# Sheet1.net
KiCad netlist of a schematic drawn in Altium Designer
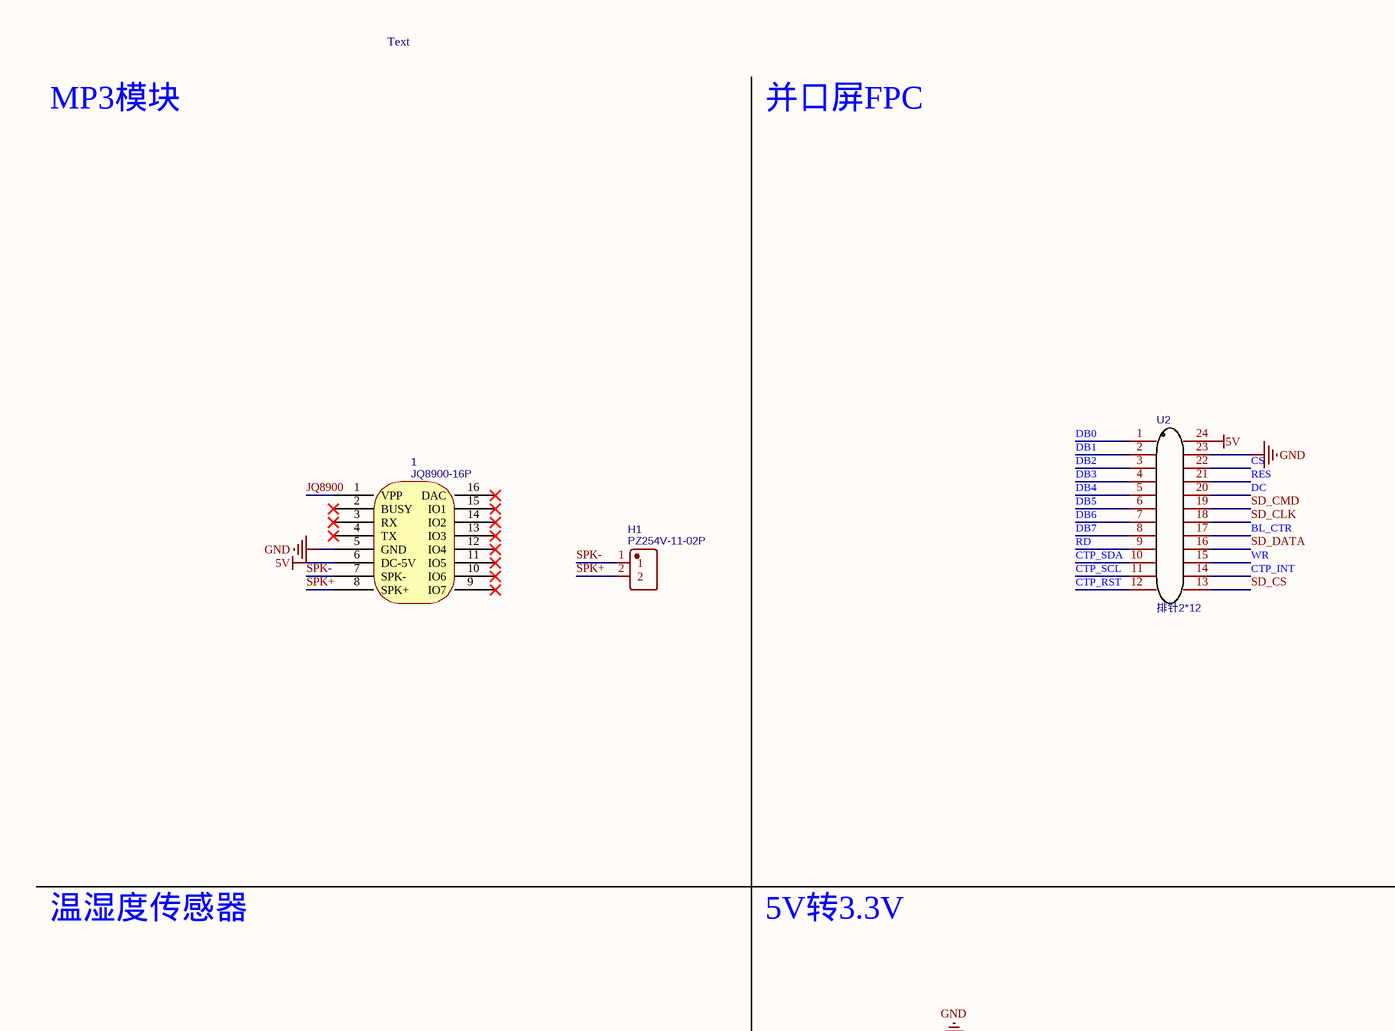
[diagram p0: Sheet1.SchDoc, top left]
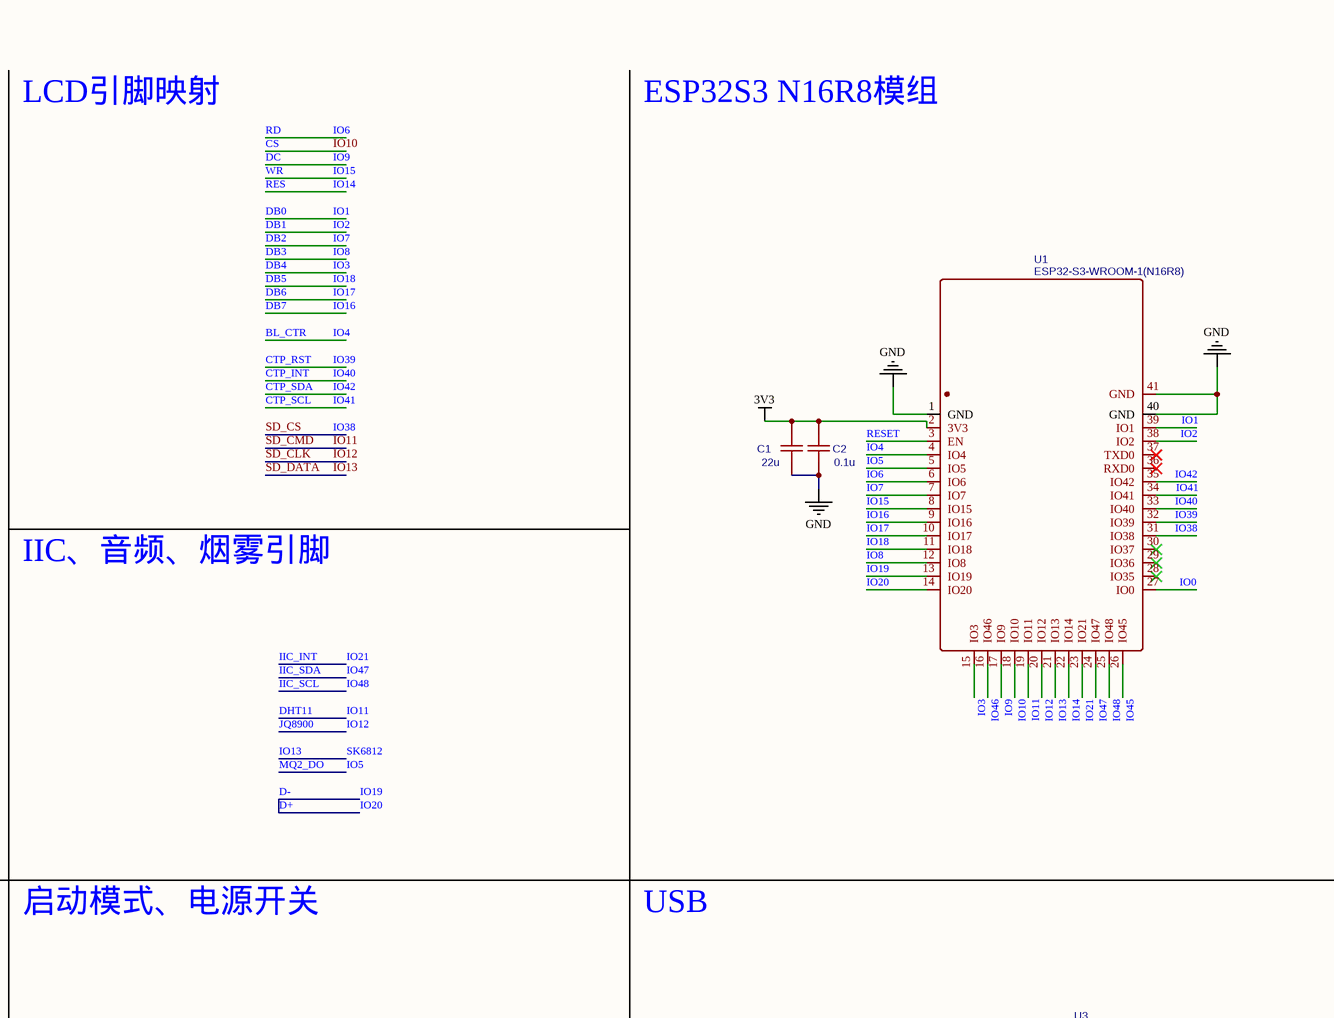
[diagram p1: Sheet1.SchDoc, top right]
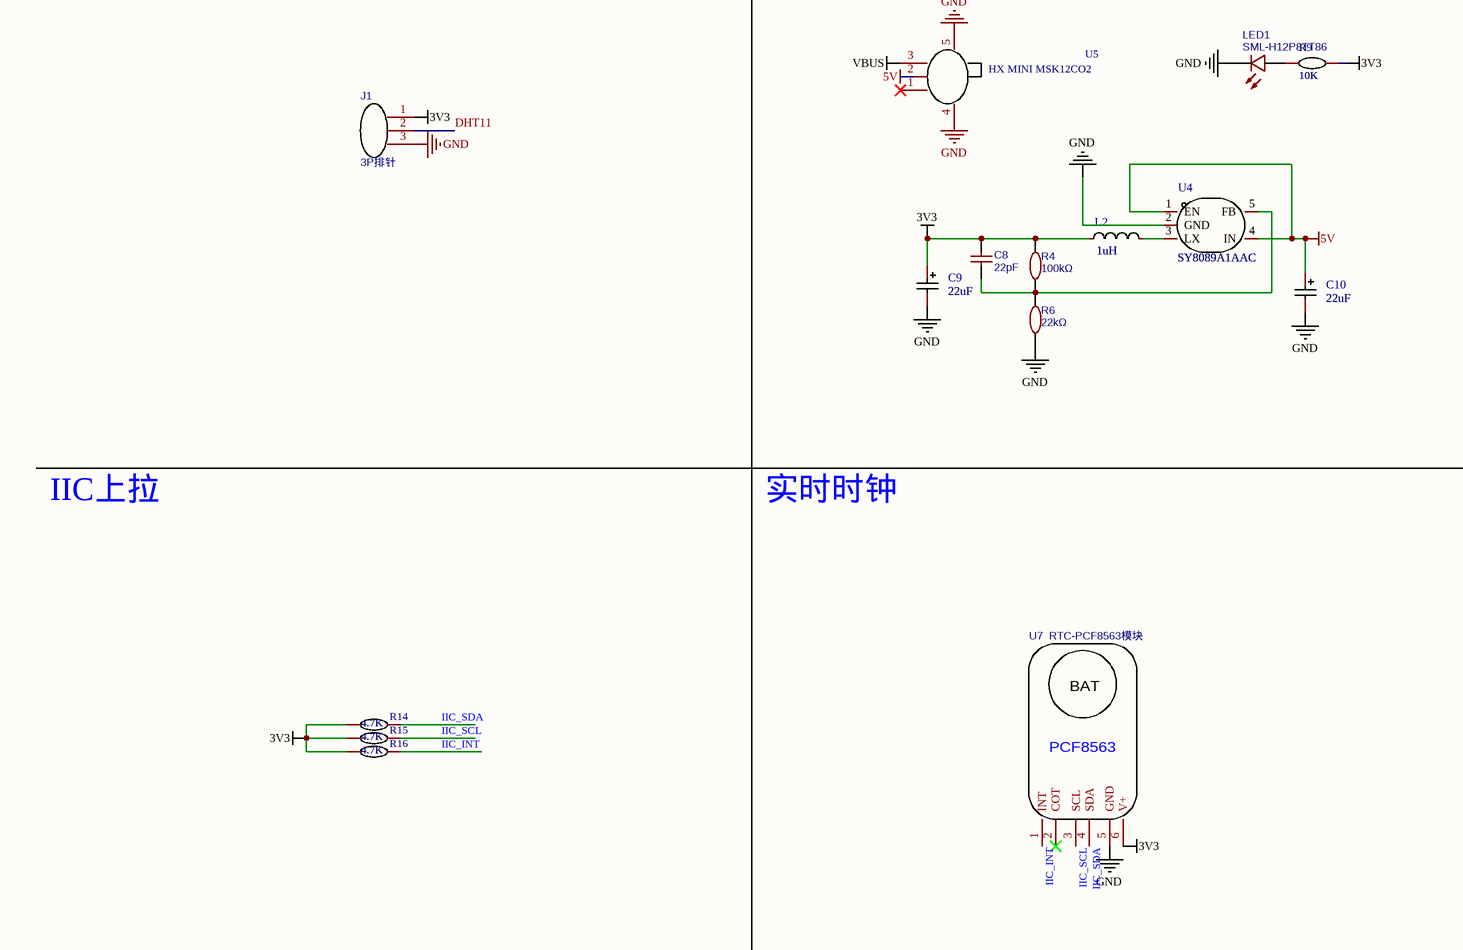
[diagram p2: Sheet1.SchDoc, bottom left]
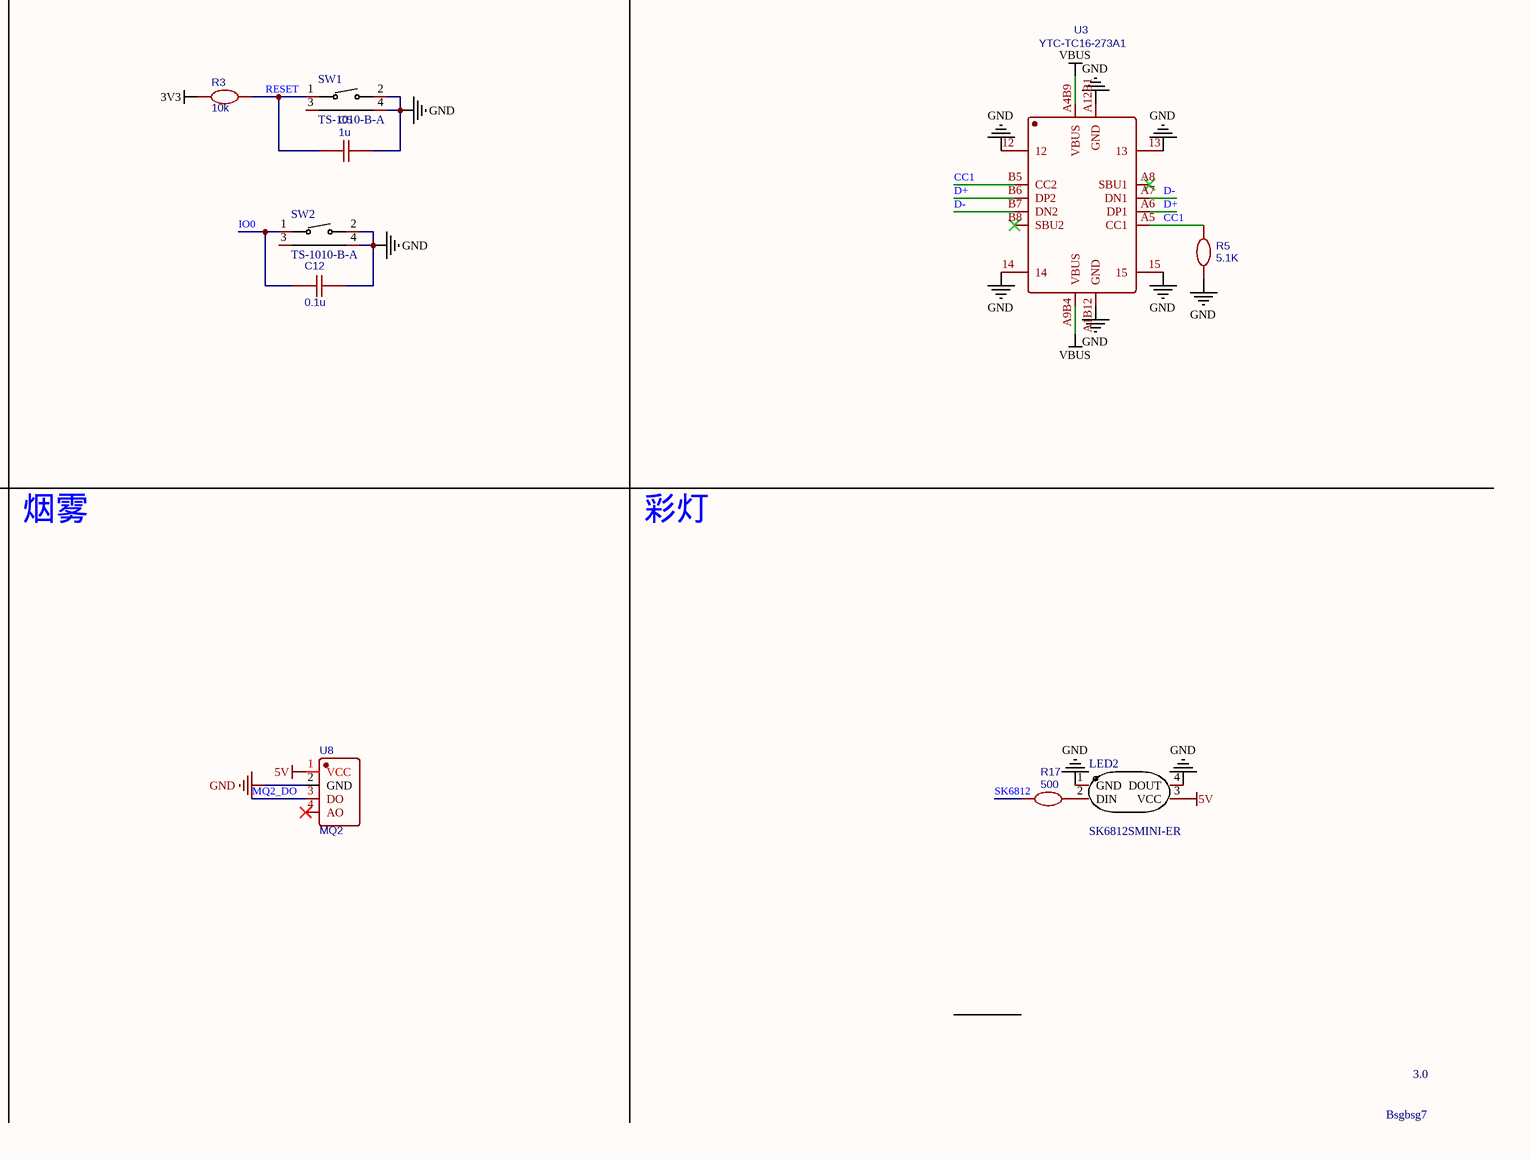
[diagram p3: Sheet1.SchDoc, bottom right]

(export (version "E")
  (design (tool "Eeschema 10.0.6"))
  (components
    (comp (ref "1")
      (value "JQ8900-16P")
      (footprint "JQ8900-16P")
      (fields (field (name "CONTRIBUTOR") "gfd1"))
      (libsource (lib "altium-import") (part "root_0_JQ8900-16P_"))
    )
    (comp (ref "C1")
      (value "22u")
      (footprint "C0603")
      (fields (field (name "CONTRIBUTOR") "LCEDA_Lib"))
      (libsource (lib "altium-import") (part "root_3_22u_"))
    )
    (comp (ref "C2")
      (value "0.1u")
      (footprint "C0603")
      (fields (field (name "CONTRIBUTOR") "LCEDA_Lib"))
      (libsource (lib "altium-import") (part "root_1_0.1u_"))
    )
    (comp (ref "C5")
      (value "1u")
      (footprint "C0603")
      (fields (field (name "CONTRIBUTOR") "LCEDA_Lib"))
      (libsource (lib "altium-import") (part "root_0_1u_"))
    )
    (comp (ref "C8")
      (value "22pF")
      (footprint "C0603")
      (fields
        (field (name "BOM_MANUFACTURER PART") "CL10C220JB8NNNC")
        (field (name "BOM_SUPPLIER PART") "C1653")
      )
      (libsource (lib "Schlib1") (part "22pF"))
    )
    (comp (ref "C9")
      (value "22uF")
      (footprint "CASE-B_3528")
      (description "容值:22uF;精度:±10%;额定电压:16V;等效串联电阻:2.3Ω@100kHz;工作温度:-55℃~+125℃;")
      (fields
        (field (name "NAME") "22uF")
        (field (name "MANUFACTURER") "Kyocera AVX")
        (field (name "MANUFACTURER PART") "TAJB226K016RNJ")
      )
      (libsource (lib "altium-import") (part "root_1_TAJB226K016RNJ_"))
    )
    (comp (ref "C10")
      (value "22uF")
      (footprint "CASE-B_3528")
      (description "容值:22uF;精度:±10%;额定电压:16V;等效串联电阻:2.3Ω@100kHz;工作温度:-55℃~+125℃;")
      (fields
        (field (name "NAME") "22uF")
        (field (name "MANUFACTURER") "Kyocera AVX")
        (field (name "MANUFACTURER PART") "TAJB226K016RNJ")
      )
      (libsource (lib "altium-import") (part "root_1_TAJB226K016RNJ_"))
    )
    (comp (ref "C12")
      (value "0.1u")
      (footprint "C0603")
      (fields (field (name "CONTRIBUTOR") "LCEDA_Lib"))
      (libsource (lib "altium-import") (part "root_2_0.1u_"))
    )
    (comp (ref "H1")
      (value "PZ254V-11-02P")
      (footprint "HDR-TH_2P-P2.54-V-M")
      (fields (field (name "BOM_SUPPLIER PART") "C492401") (field (name "CONTRIBUTOR") "LCSC"))
      (libsource (lib "altium-import") (part "root_0_PZ254V-11-02P_"))
    )
    (comp (ref "J1")
      (value "3P排针")
      (footprint "DHT")
      (fields (field (name "CONTRIBUTOR") "878738424"))
      (libsource (lib "Schlib1") (part "3P排针"))
    )
    (comp (ref "L2")
      (value "1uH")
      (footprint "IND-SMD_L3.2-W3.2-1")
      (description "电感值:1uH;精度:±20%;额定电流:4A;直流电阻(DCR):32mΩ;")
      (fields
        (field (name "NAME") "1uH")
        (field (name "MANUFACTURER") "TAI-TECH(台庆)")
        (field (name "MANUFACTURER PART") "TMPC0302H-1R0MG")
      )
      (libsource (lib "altium-import") (part "root_0_TMPC0302H-1R0MG_"))
    )
    (comp (ref "LED1")
      (value "SML-H12P8TT86")
      (footprint "LED0805-R-RD_GREEN")
      (fields (field (name "BOM_SUPPLIER PART") "C510035") (field (name "CONTRIBUTOR") "lcsc"))
      (libsource (lib "altium-import") (part "root_2_SML-H12P8TT86_"))
    )
    (comp (ref "LED2")
      (value "SK6812SMINI-ER")
      (footprint "SK6812")
      (fields (field (name "MANUFACTURER") "欧思科光电") (field (name "NAME") "SK6812SMINI-ER"))
      (libsource (lib "Integrated_Library1") (part "SK6812SMINI-ER"))
    )
    (comp (ref "R3")
      (value "10k")
      (footprint "R0603")
      (fields (field (name "CONTRIBUTOR") "LCEDA_Lib"))
      (libsource (lib "altium-import") (part "root_0_5.1K_"))
    )
    (comp (ref "R4")
      (value "100kΩ")
      (footprint "R0603")
      (fields
        (field (name "BOM_MANUFACTURER PART") "0603WAF1003T5E")
        (field (name "BOM_SUPPLIER PART") "C25803")
      )
      (libsource (lib "Schlib1") (part "100kΩ"))
    )
    (comp (ref "R5")
      (value "5.1K")
      (footprint "R0603")
      (fields (field (name "CONTRIBUTOR") "LCEDA_Lib"))
      (libsource (lib "altium-import") (part "root_3_5.1K_"))
    )
    (comp (ref "R6")
      (value "22kΩ")
      (footprint "R0603")
      (fields
        (field (name "BOM_MANUFACTURER PART") "0603WAF2202T5E")
        (field (name "BOM_SUPPLIER PART") "C31850")
      )
      (libsource (lib "Schlib1") (part "22kΩ"))
    )
    (comp (ref "R9") (value "10K") (footprint "R0603") (libsource (lib "altium-import") (part "root_0_10K_")))
    (comp (ref "R14")
      (value "4.7K")
      (footprint "R0603")
      (fields (field (name "MANUFACTURER") "YAGEO") (field (name "MANUFACTURER PART") "AF0603FR-0710KL"))
      (libsource (lib "altium-import") (part "root_0_4.7K_"))
    )
    (comp (ref "R15")
      (value "4.7K")
      (footprint "R0603")
      (fields (field (name "MANUFACTURER") "YAGEO") (field (name "MANUFACTURER PART") "AF0603FR-0710KL"))
      (libsource (lib "altium-import") (part "root_0_4.7K_"))
    )
    (comp (ref "R16")
      (value "4.7K")
      (footprint "R0603")
      (fields (field (name "MANUFACTURER") "YAGEO") (field (name "MANUFACTURER PART") "AF0603FR-0710KL"))
      (libsource (lib "altium-import") (part "root_0_4.7K_"))
    )
    (comp (ref "R17")
      (value "500")
      (footprint "R0603")
      (fields (field (name "CONTRIBUTOR") "LCEDA_Lib"))
      (libsource (lib "altium-import") (part "root_0_1.2K_"))
    )
    (comp (ref "SW1")
      (value "TS-1010-B-A")
      (footprint "PcbLib1:KEY-SMD_TX-1010-X-X")
      (fields (field (name "MANUFACTURER") "XKB Connectivity(中国星坤)"))
      (libsource (lib "Integrated_Library1") (part "TS-1010-B-A"))
    )
    (comp (ref "SW2")
      (value "TS-1010-B-A")
      (footprint "PcbLib1:KEY-SMD_TX-1010-X-X")
      (fields (field (name "MANUFACTURER") "XKB Connectivity(中国星坤)"))
      (libsource (lib "Integrated_Library1") (part "TS-1010-B-A"))
    )
    (comp (ref "U1")
      (value "ESP32-S3-WROOM-1(N16R8)")
      (footprint "WIRELM-SMD_ESP32-S3-WROOM-1")
      (fields
        (field (name "BOM_SUPPLIER PART") "C2913202")
        (field (name "BOM_MANUFACTURER PART") "ESP32-S3-WROOM-1-N16R8")
        (field (name "CONTRIBUTOR") "lcsc")
      )
      (libsource (lib "altium-import") (part "root_0_ESP32-S3-WROOM-1(N16R8)_"))
    )
    (comp (ref "U2")
      (value "排针2*12")
      (footprint "PCBComponent_1 - duplicate")
      (fields (field (name "CONTRIBUTOR") "Leshushi"))
      (libsource (lib "Schlib1") (part "排针2*12"))
    )
    (comp (ref "U3")
      (value "YTC-TC16-273A1")
      (footprint "TYPE-C-SMD_YIYUAN_YTC-TC16-273A1")
      (fields (field (name "BOM_SUPPLIER PART") "C5260486") (field (name "CONTRIBUTOR") "lcsc"))
      (libsource (lib "altium-import") (part "root_0_YTC-TC16-273A1_"))
    )
    (comp (ref "U4")
      (value "SY8089A1AAC")
      (footprint "TSOT-23-5_L2.9-W1.6-P0.95-LS2.8-BR")
      (fields (field (name "NAME") "SY8089A1AAC") (field (name "MANUFACTURER") "silergy(矽力杰)"))
      (libsource (lib "altium-import") (part "root_0_SY8089A1AAC_"))
    )
    (comp (ref "U5")
      (value "HX MINI MSK12CO2")
      (footprint "SW-SMD_MSK12CO2")
      (fields (field (name "MANUFACTURER") "hanxia(韩下)"))
      (libsource (lib "Schlib1") (part "HX MINI MSK12CO2"))
    )
    (comp (ref "U7")
      (value "RTC-PCF8563模块")
      (footprint "PCF8563模块")
      (fields (field (name "BOM_MANUFACTURER PART") "Xu4388") (field (name "CONTRIBUTOR") "XDesign"))
      (libsource (lib "Integrated_Library1") (part "RTC-PCF8563模块"))
    )
    (comp (ref "U8")
      (value "MQ2")
      (footprint "MQ2")
      (fields (field (name "CONTRIBUTOR") "1898stark"))
      (libsource (lib "Integrated_Library1") (part "MQ2"))
    )
  )
  (nets
    (net (code "1") (name "/BL_CTR") (class "Default")
      (node (ref "U1") (pin "4") (pinfunction "IO4_4") (pintype "passive"))
      (node (ref "U2") (pin "17") (pinfunction "17_17") (pintype "passive"))
    )
    (net (code "2") (name "/CC1") (class "Default")
      (node (ref "R5") (pin "1") (pinfunction "1_1") (pintype "passive"))
      (node (ref "U3") (pin "A5") (pinfunction "CC1_A5") (pintype "passive"))
      (node (ref "U3") (pin "B5") (pinfunction "CC2_B5") (pintype "passive"))
    )
    (net (code "3") (name "/CS") (class "Default")
      (node (ref "U1") (pin "18") (pinfunction "IO10_18") (pintype "passive"))
      (node (ref "U2") (pin "22") (pinfunction "22_22") (pintype "passive"))
    )
    (net (code "4") (name "/CTP_INT") (class "Default")
      (node (ref "U1") (pin "33") (pinfunction "IO40_33") (pintype "passive"))
      (node (ref "U2") (pin "14") (pinfunction "14_14") (pintype "passive"))
    )
    (net (code "5") (name "/CTP_RST") (class "Default")
      (node (ref "U1") (pin "32") (pinfunction "IO39_32") (pintype "passive"))
      (node (ref "U2") (pin "12") (pinfunction "12_12") (pintype "passive"))
    )
    (net (code "6") (name "/CTP_SCL") (class "Default")
      (node (ref "U1") (pin "34") (pinfunction "IO41_34") (pintype "passive"))
      (node (ref "U2") (pin "11") (pinfunction "11_11") (pintype "passive"))
    )
    (net (code "7") (name "/CTP_SDA") (class "Default")
      (node (ref "U1") (pin "35") (pinfunction "IO42_35") (pintype "passive"))
      (node (ref "U2") (pin "10") (pinfunction "10_10") (pintype "passive"))
    )
    (net (code "8") (name "/D+") (class "Default")
      (node (ref "U1") (pin "13") (pinfunction "IO19_13") (pintype "passive"))
      (node (ref "U1") (pin "14") (pinfunction "IO20_14") (pintype "passive"))
      (node (ref "U3") (pin "A6") (pinfunction "DP1_A6") (pintype "passive"))
      (node (ref "U3") (pin "A7") (pinfunction "DN1_A7") (pintype "passive"))
      (node (ref "U3") (pin "B6") (pinfunction "DP2_B6") (pintype "passive"))
      (node (ref "U3") (pin "B7") (pinfunction "DN2_B7") (pintype "passive"))
    )
    (net (code "9") (name "/DB0") (class "Default")
      (node (ref "U1") (pin "39") (pinfunction "IO1_39") (pintype "passive"))
      (node (ref "U2") (pin "1") (pinfunction "1_1") (pintype "passive"))
    )
    (net (code "10") (name "/DB1") (class "Default")
      (node (ref "U1") (pin "38") (pinfunction "IO2_38") (pintype "passive"))
      (node (ref "U2") (pin "2") (pinfunction "2_2") (pintype "passive"))
    )
    (net (code "11") (name "/DB2") (class "Default")
      (node (ref "U1") (pin "7") (pinfunction "IO7_7") (pintype "passive"))
      (node (ref "U2") (pin "3") (pinfunction "3_3") (pintype "passive"))
    )
    (net (code "12") (name "/DB3") (class "Default")
      (node (ref "U1") (pin "12") (pinfunction "IO8_12") (pintype "passive"))
      (node (ref "U2") (pin "4") (pinfunction "4_4") (pintype "passive"))
    )
    (net (code "13") (name "/DB4") (class "Default")
      (node (ref "U1") (pin "15") (pinfunction "IO3_15") (pintype "passive"))
      (node (ref "U2") (pin "5") (pinfunction "5_5") (pintype "passive"))
    )
    (net (code "14") (name "/DB5") (class "Default")
      (node (ref "U1") (pin "11") (pinfunction "IO18_11") (pintype "passive"))
      (node (ref "U2") (pin "6") (pinfunction "6_6") (pintype "passive"))
    )
    (net (code "15") (name "/DB6") (class "Default")
      (node (ref "U1") (pin "10") (pinfunction "IO17_10") (pintype "passive"))
      (node (ref "U2") (pin "7") (pinfunction "7_7") (pintype "passive"))
    )
    (net (code "16") (name "/DB7") (class "Default")
      (node (ref "U1") (pin "9") (pinfunction "IO16_9") (pintype "passive"))
      (node (ref "U2") (pin "8") (pinfunction "8_8") (pintype "passive"))
    )
    (net (code "17") (name "/DC") (class "Default")
      (node (ref "U1") (pin "17") (pinfunction "IO9_17") (pintype "passive"))
      (node (ref "U2") (pin "20") (pinfunction "20_20") (pintype "passive"))
    )
    (net (code "18") (name "/DHT11") (class "Default")
      (node (ref "J1") (pin "2") (pinfunction "2_2") (pintype "passive"))
      (node (ref "U1") (pin "19") (pinfunction "IO11_19") (pintype "passive"))
      (node (ref "U2") (pin "19") (pinfunction "19_19") (pintype "passive"))
    )
    (net (code "19") (name "/IIC_INT") (class "Default")
      (node (ref "R16") (pin "2") (pinfunction "2_2") (pintype "passive"))
      (node (ref "U1") (pin "23") (pinfunction "IO21_23") (pintype "passive"))
      (node (ref "U7") (pin "1") (pinfunction "INT_1") (pintype "passive"))
    )
    (net (code "20") (name "/IIC_SCL") (class "Default")
      (node (ref "R15") (pin "2") (pinfunction "2_2") (pintype "passive"))
      (node (ref "U1") (pin "25") (pinfunction "IO48_25") (pintype "passive"))
      (node (ref "U7") (pin "3") (pinfunction "SCL_3") (pintype "passive"))
    )
    (net (code "21") (name "/IIC_SDA") (class "Default")
      (node (ref "R14") (pin "2") (pinfunction "2_2") (pintype "passive"))
      (node (ref "U1") (pin "24") (pinfunction "IO47_24") (pintype "passive"))
      (node (ref "U7") (pin "4") (pinfunction "SDA_4") (pintype "passive"))
    )
    (net (code "22") (name "/IO0") (class "Default")
      (node (ref "C12") (pin "2") (pinfunction "2_2") (pintype "passive"))
      (node (ref "SW2") (pin "1") (pinfunction "1_1") (pintype "passive"))
      (node (ref "U1") (pin "27") (pinfunction "IO0_27") (pintype "passive"))
    )
    (net (code "23") (name "/IO5") (class "Default")
      (node (ref "U1") (pin "5") (pinfunction "IO5_5") (pintype "passive"))
      (node (ref "U8") (pin "3") (pinfunction "DO_3") (pintype "passive"))
    )
    (net (code "24") (name "/IO6") (class "Default")
      (node (ref "U1") (pin "6") (pinfunction "IO6_6") (pintype "passive"))
      (node (ref "U2") (pin "9") (pinfunction "9_9") (pintype "passive"))
    )
    (net (code "25") (name "/IO12") (class "Default")
      (node (ref "1") (pin "1") (pinfunction "VPP_1") (pintype "passive"))
      (node (ref "U1") (pin "20") (pinfunction "IO12_20") (pintype "passive"))
      (node (ref "U2") (pin "18") (pinfunction "18_18") (pintype "passive"))
    )
    (net (code "26") (name "/IO13") (class "Default")
      (node (ref "R17") (pin "1") (pinfunction "1_1") (pintype "passive"))
      (node (ref "U1") (pin "21") (pinfunction "IO13_21") (pintype "passive"))
      (node (ref "U2") (pin "16") (pinfunction "16_16") (pintype "passive"))
    )
    (net (code "27") (name "/IO14") (class "Default")
      (node (ref "U1") (pin "22") (pinfunction "IO14_22") (pintype "passive"))
      (node (ref "U2") (pin "21") (pinfunction "21_21") (pintype "passive"))
    )
    (net (code "28") (name "/IO15") (class "Default")
      (node (ref "U1") (pin "8") (pinfunction "IO15_8") (pintype "passive"))
      (node (ref "U2") (pin "15") (pinfunction "15_15") (pintype "passive"))
    )
    (net (code "29") (name "/IO38") (class "Default")
      (node (ref "U1") (pin "31") (pinfunction "IO38_31") (pintype "passive"))
      (node (ref "U2") (pin "13") (pinfunction "13_13") (pintype "passive"))
    )
    (net (code "30") (name "/IO45") (class "Default")
      (node (ref "U1") (pin "26") (pinfunction "IO45_26") (pintype "passive"))
    )
    (net (code "31") (name "/IO46") (class "Default")
      (node (ref "U1") (pin "16") (pinfunction "IO46_16") (pintype "passive"))
    )
    (net (code "32") (name "/RESET") (class "Default")
      (node (ref "C5") (pin "1") (pinfunction "1_1") (pintype "passive"))
      (node (ref "R3") (pin "2") (pinfunction "2_2") (pintype "passive"))
      (node (ref "SW1") (pin "1") (pinfunction "1_1") (pintype "passive"))
      (node (ref "U1") (pin "3") (pinfunction "EN_3") (pintype "passive"))
    )
    (net (code "33") (name "/SPK+") (class "Default")
      (node (ref "1") (pin "8") (pinfunction "SPK+_8") (pintype "passive"))
      (node (ref "H1") (pin "2") (pinfunction "2_2") (pintype "passive"))
    )
    (net (code "34") (name "/SPK-") (class "Default")
      (node (ref "1") (pin "7") (pinfunction "SPK-_7") (pintype "passive"))
      (node (ref "H1") (pin "1") (pinfunction "1_1") (pintype "passive"))
    )
    (net (code "35") (name "3V3") (class "Default")
      (node (ref "C1") (pin "1") (pinfunction "1_1") (pintype "passive"))
      (node (ref "C2") (pin "2") (pinfunction "2_2") (pintype "passive"))
      (node (ref "C8") (pin "2") (pinfunction "2_2") (pintype "passive"))
      (node (ref "C9") (pin "1") (pinfunction "1_1") (pintype "passive"))
      (node (ref "J1") (pin "1") (pinfunction "1_1") (pintype "passive"))
      (node (ref "L2") (pin "1") (pinfunction "1_1") (pintype "passive"))
      (node (ref "R14") (pin "1") (pinfunction "1_1") (pintype "passive"))
      (node (ref "R15") (pin "1") (pinfunction "1_1") (pintype "passive"))
      (node (ref "R16") (pin "1") (pinfunction "1_1") (pintype "passive"))
      (node (ref "R3") (pin "1") (pinfunction "1_1") (pintype "passive"))
      (node (ref "R4") (pin "2") (pinfunction "2_2") (pintype "passive"))
      (node (ref "R9") (pin "2") (pinfunction "2_2") (pintype "passive"))
      (node (ref "U1") (pin "2") (pinfunction "3V3_2") (pintype "passive"))
      (node (ref "U7") (pin "6") (pinfunction "V+_6") (pintype "passive"))
    )
    (net (code "36") (name "5V") (class "Default")
      (node (ref "1") (pin "6") (pinfunction "DC-5V_6") (pintype "passive"))
      (node (ref "C10") (pin "1") (pinfunction "1_1") (pintype "passive"))
      (node (ref "LED2") (pin "3") (pinfunction "VCC_3") (pintype "passive"))
      (node (ref "U2") (pin "24") (pinfunction "24_24") (pintype "passive"))
      (node (ref "U4") (pin "1") (pinfunction "EN_1") (pintype "passive"))
      (node (ref "U4") (pin "4") (pinfunction "IN_4") (pintype "passive"))
      (node (ref "U5") (pin "2") (pinfunction "2_2") (pintype "passive"))
      (node (ref "U8") (pin "1") (pinfunction "VCC_1") (pintype "passive"))
    )
    (net (code "37") (name "GND") (class "Default")
      (node (ref "1") (pin "5") (pinfunction "GND_5") (pintype "passive"))
      (node (ref "C1") (pin "2") (pinfunction "2_2") (pintype "passive"))
      (node (ref "C10") (pin "2") (pinfunction "2_2") (pintype "passive"))
      (node (ref "C12") (pin "1") (pinfunction "1_1") (pintype "passive"))
      (node (ref "C2") (pin "1") (pinfunction "1_1") (pintype "passive"))
      (node (ref "C5") (pin "2") (pinfunction "2_2") (pintype "passive"))
      (node (ref "C9") (pin "2") (pinfunction "2_2") (pintype "passive"))
      (node (ref "J1") (pin "3") (pinfunction "3_3") (pintype "passive"))
      (node (ref "LED1") (pin "2") (pinfunction "C_2") (pintype "passive"))
      (node (ref "LED2") (pin "1") (pinfunction "GND_1") (pintype "passive"))
      (node (ref "LED2") (pin "4") (pinfunction "DOUT_4") (pintype "passive"))
      (node (ref "R5") (pin "2") (pinfunction "2_2") (pintype "passive"))
      (node (ref "R6") (pin "1") (pinfunction "1_1") (pintype "passive"))
      (node (ref "SW1") (pin "2") (pinfunction "2_2") (pintype "passive"))
      (node (ref "SW1") (pin "4") (pinfunction "4_4") (pintype "passive"))
      (node (ref "SW2") (pin "2") (pinfunction "2_2") (pintype "passive"))
      (node (ref "SW2") (pin "4") (pinfunction "4_4") (pintype "passive"))
      (node (ref "U1") (pin "1") (pinfunction "GND_1") (pintype "passive"))
      (node (ref "U1") (pin "40") (pinfunction "GND_40") (pintype "passive"))
      (node (ref "U1") (pin "41") (pinfunction "GND_41") (pintype "passive"))
      (node (ref "U2") (pin "23") (pinfunction "23_23") (pintype "passive"))
      (node (ref "U3") (pin "12") (pinfunction "12_12") (pintype "passive"))
      (node (ref "U3") (pin "13") (pinfunction "13_13") (pintype "passive"))
      (node (ref "U3") (pin "14") (pinfunction "14_14") (pintype "passive"))
      (node (ref "U3") (pin "15") (pinfunction "15_15") (pintype "passive"))
      (node (ref "U3") (pin "A12B1") (pinfunction "GND_A12B1") (pintype "passive"))
      (node (ref "U3") (pin "A1B12") (pinfunction "GND_A1B12") (pintype "passive"))
      (node (ref "U4") (pin "2") (pinfunction "GND_2") (pintype "passive"))
      (node (ref "U5") (pin "4") (pinfunction "4_4") (pintype "passive"))
      (node (ref "U5") (pin "5") (pinfunction "5_5") (pintype "passive"))
      (node (ref "U7") (pin "5") (pinfunction "GND_5") (pintype "passive"))
      (node (ref "U8") (pin "2") (pinfunction "GND_2") (pintype "passive"))
    )
    (net (code "38") (name "Net-(LED1-A)") (class "Default")
      (node (ref "LED1") (pin "1") (pinfunction "A_1") (pintype "passive"))
      (node (ref "R9") (pin "1") (pinfunction "1_1") (pintype "passive"))
    )
    (net (code "39") (name "Net-(LED2-DIN)") (class "Default")
      (node (ref "LED2") (pin "2") (pinfunction "DIN_2") (pintype "passive"))
      (node (ref "R17") (pin "2") (pinfunction "2_2") (pintype "passive"))
    )
    (net (code "40") (name "Net-(U4-FB)") (class "Default")
      (node (ref "C8") (pin "1") (pinfunction "1_1") (pintype "passive"))
      (node (ref "R4") (pin "1") (pinfunction "1_1") (pintype "passive"))
      (node (ref "R6") (pin "2") (pinfunction "2_2") (pintype "passive"))
      (node (ref "U4") (pin "5") (pinfunction "FB_5") (pintype "passive"))
    )
    (net (code "41") (name "Net-(U4-LX)") (class "Default")
      (node (ref "L2") (pin "2") (pinfunction "2_2") (pintype "passive"))
      (node (ref "U4") (pin "3") (pinfunction "LX_3") (pintype "passive"))
    )
    (net (code "42") (name "VBUS") (class "Default")
      (node (ref "U3") (pin "A4B9") (pinfunction "VBUS_A4B9") (pintype "passive"))
      (node (ref "U3") (pin "A9B4") (pinfunction "VBUS_A9B4") (pintype "passive"))
      (node (ref "U5") (pin "3") (pinfunction "3_3") (pintype "passive"))
    )
    (net (code "43") (name "unconnected-(1-BUSY-Pad2)") (class "Default")
      (node (ref "1") (pin "2") (pinfunction "BUSY_2") (pintype "passive+no_connect"))
    )
    (net (code "44") (name "unconnected-(1-DAC-Pad16)") (class "Default")
      (node (ref "1") (pin "16") (pinfunction "DAC_16") (pintype "passive+no_connect"))
    )
    (net (code "45") (name "unconnected-(1-IO1-Pad15)") (class "Default")
      (node (ref "1") (pin "15") (pinfunction "IO1_15") (pintype "passive+no_connect"))
    )
    (net (code "46") (name "unconnected-(1-IO2-Pad14)") (class "Default")
      (node (ref "1") (pin "14") (pinfunction "IO2_14") (pintype "passive+no_connect"))
    )
    (net (code "47") (name "unconnected-(1-IO3-Pad13)") (class "Default")
      (node (ref "1") (pin "13") (pinfunction "IO3_13") (pintype "passive+no_connect"))
    )
    (net (code "48") (name "unconnected-(1-IO4-Pad12)") (class "Default")
      (node (ref "1") (pin "12") (pinfunction "IO4_12") (pintype "passive+no_connect"))
    )
    (net (code "49") (name "unconnected-(1-IO5-Pad11)") (class "Default")
      (node (ref "1") (pin "11") (pinfunction "IO5_11") (pintype "passive+no_connect"))
    )
    (net (code "50") (name "unconnected-(1-IO6-Pad10)") (class "Default")
      (node (ref "1") (pin "10") (pinfunction "IO6_10") (pintype "passive+no_connect"))
    )
    (net (code "51") (name "unconnected-(1-IO7-Pad9)") (class "Default")
      (node (ref "1") (pin "9") (pinfunction "IO7_9") (pintype "passive+no_connect"))
    )
    (net (code "52") (name "unconnected-(1-RX-Pad3)") (class "Default")
      (node (ref "1") (pin "3") (pinfunction "RX_3") (pintype "passive+no_connect"))
    )
    (net (code "53") (name "unconnected-(1-TX-Pad4)") (class "Default")
      (node (ref "1") (pin "4") (pinfunction "TX_4") (pintype "passive+no_connect"))
    )
    (net (code "54") (name "unconnected-(SW1-Pad3)") (class "Default")
      (node (ref "SW1") (pin "3") (pinfunction "3_3") (pintype "passive"))
    )
    (net (code "55") (name "unconnected-(SW2-Pad3)") (class "Default")
      (node (ref "SW2") (pin "3") (pinfunction "3_3") (pintype "passive"))
    )
    (net (code "56") (name "unconnected-(U1-IO35-Pad28)") (class "Default")
      (node (ref "U1") (pin "28") (pinfunction "IO35_28") (pintype "passive+no_connect"))
    )
    (net (code "57") (name "unconnected-(U1-IO36-Pad29)") (class "Default")
      (node (ref "U1") (pin "29") (pinfunction "IO36_29") (pintype "passive+no_connect"))
    )
    (net (code "58") (name "unconnected-(U1-IO37-Pad30)") (class "Default")
      (node (ref "U1") (pin "30") (pinfunction "IO37_30") (pintype "passive+no_connect"))
    )
    (net (code "59") (name "unconnected-(U1-RXD0-Pad36)") (class "Default")
      (node (ref "U1") (pin "36") (pinfunction "RXD0_36") (pintype "passive+no_connect"))
    )
    (net (code "60") (name "unconnected-(U1-TXD0-Pad37)") (class "Default")
      (node (ref "U1") (pin "37") (pinfunction "TXD0_37") (pintype "passive+no_connect"))
    )
    (net (code "61") (name "unconnected-(U3-SBU1-PadA8)") (class "Default")
      (node (ref "U3") (pin "A8") (pinfunction "SBU1_A8") (pintype "passive+no_connect"))
    )
    (net (code "62") (name "unconnected-(U3-SBU2-PadB8)") (class "Default")
      (node (ref "U3") (pin "B8") (pinfunction "SBU2_B8") (pintype "passive+no_connect"))
    )
    (net (code "63") (name "unconnected-(U5-Pad1)") (class "Default")
      (node (ref "U5") (pin "1") (pinfunction "1_1") (pintype "passive+no_connect"))
    )
    (net (code "64") (name "unconnected-(U7-COT-Pad2)") (class "Default")
      (node (ref "U7") (pin "2") (pinfunction "COT_2") (pintype "passive+no_connect"))
    )
    (net (code "65") (name "unconnected-(U8-AO-Pad4)") (class "Default")
      (node (ref "U8") (pin "4") (pinfunction "AO_4") (pintype "passive+no_connect"))
    )
  )
)
